# UC3843_Buck.net
KiCad netlist of a schematic drawn in Altium Designer
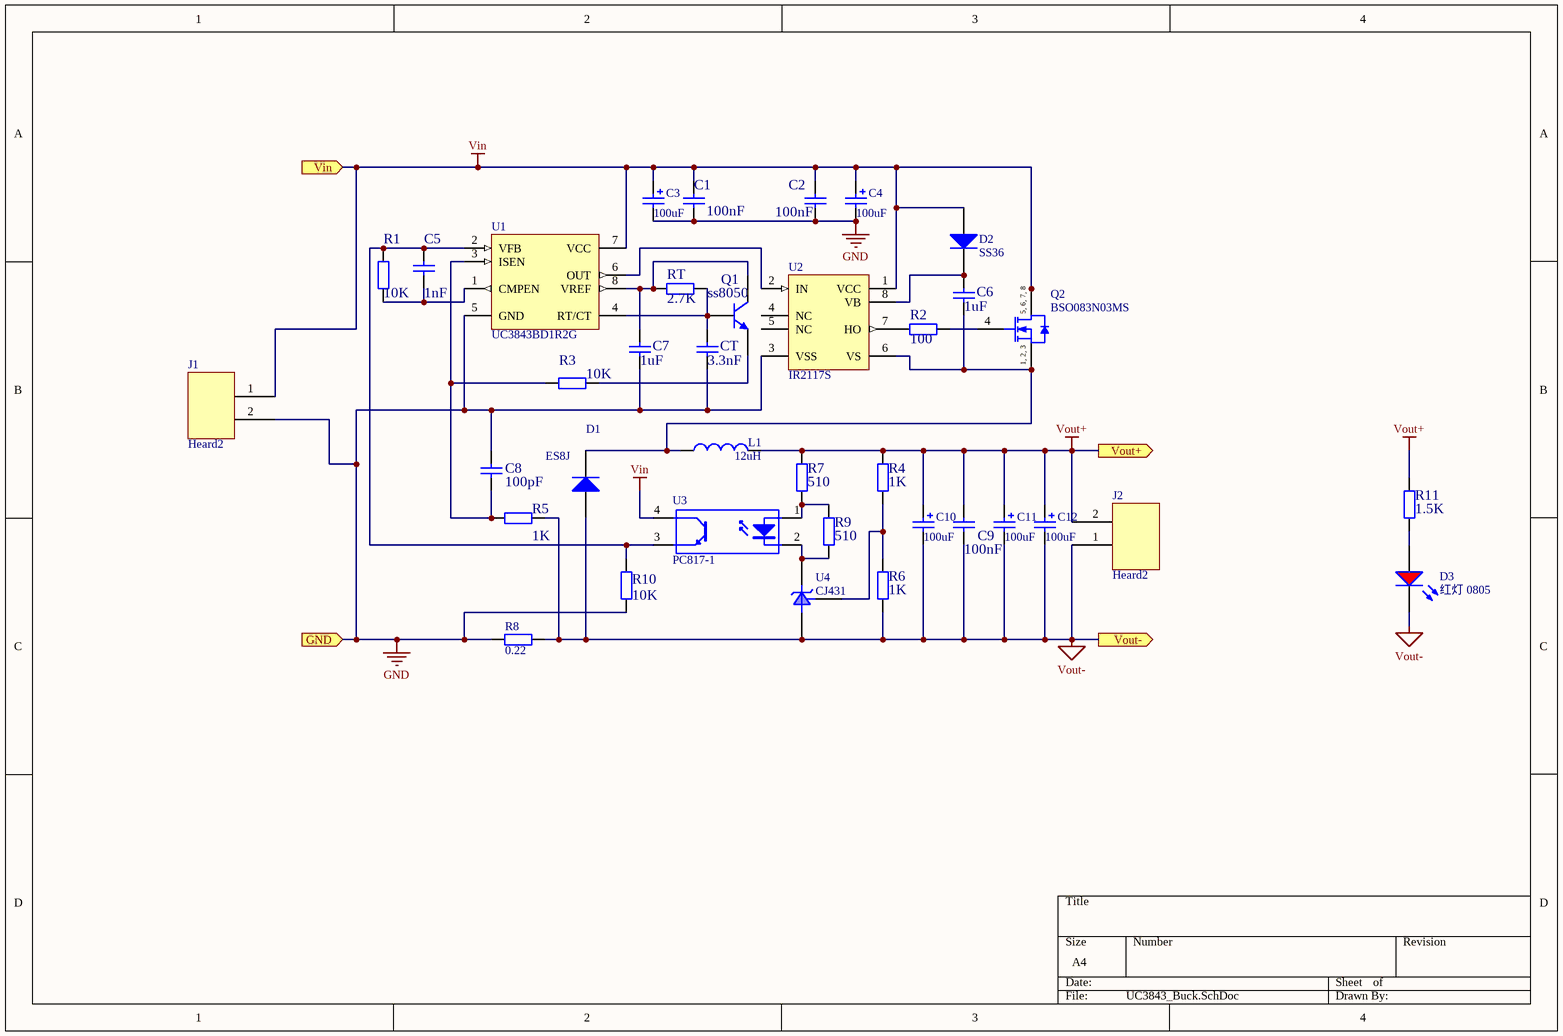
[diagram p0: UC3843_Buck.SchDoc]

(export (version "E")
  (design (tool "Eeschema 10.0.6"))
  (components
    (comp (ref "C1")
      (value "100nF")
      (footprint "0805_C")
      (description "贴片电容")
      (libsource (lib "Miscellaneous Devices LC") (part "0805 100nF(104) 10% 50V"))
    )
    (comp (ref "C2")
      (value "100nF")
      (footprint "0805_C")
      (description "贴片电容")
      (libsource (lib "Miscellaneous Devices LC") (part "0805 100nF(104) 10% 50V"))
    )
    (comp (ref "C3")
      (value "100uF")
      (footprint "CASE-B_3528")
      (description "钽电容")
      (libsource (lib "Miscellaneous Devices LC") (part "3528 100uF (107) 10% 6.3V"))
    )
    (comp (ref "C4")
      (value "100uF")
      (footprint "CASE-B_3528")
      (description "钽电容")
      (libsource (lib "Miscellaneous Devices LC") (part "3528 100uF (107) 10% 6.3V"))
    )
    (comp (ref "C5")
      (value "1nF")
      (footprint "0805_C")
      (description "贴片电容")
      (libsource (lib "Miscellaneous Devices LC") (part "0805 100nF(104) 10% 50V"))
    )
    (comp (ref "C6")
      (value "1uF")
      (footprint "0805R")
      (description "Capacitor")
      (fields (field (name "PUBLISHER") "Altium Limited"))
      (libsource (lib "Miscellaneous Devices") (part "Cap"))
    )
    (comp (ref "C7")
      (value "1uF")
      (footprint "0805R")
      (description "Capacitor")
      (fields (field (name "PUBLISHER") "Altium Limited"))
      (libsource (lib "Miscellaneous Devices") (part "Cap"))
    )
    (comp (ref "C8")
      (value "100pF")
      (footprint "0805R")
      (description "Capacitor")
      (fields (field (name "PUBLISHER") "Altium Limited"))
      (libsource (lib "Miscellaneous Devices") (part "Cap"))
    )
    (comp (ref "C9")
      (value "100nF")
      (footprint "0805_C")
      (description "贴片电容")
      (libsource (lib "Miscellaneous Devices LC") (part "0805 100nF(104) 10% 50V"))
    )
    (comp (ref "C10")
      (value "100uF")
      (footprint "CASE-B_3528")
      (description "钽电容")
      (libsource (lib "Miscellaneous Devices LC") (part "3528 100uF (107) 10% 6.3V"))
    )
    (comp (ref "C11")
      (value "100uF")
      (footprint "CASE-B_3528")
      (description "钽电容")
      (libsource (lib "Miscellaneous Devices LC") (part "3528 100uF (107) 10% 6.3V"))
    )
    (comp (ref "C12")
      (value "100uF")
      (footprint "CASE-B_3528")
      (description "钽电容")
      (libsource (lib "Miscellaneous Devices LC") (part "3528 100uF (107) 10% 6.3V"))
    )
    (comp (ref "CT")
      (value "3.3nF")
      (footprint "0805R")
      (description "Capacitor")
      (fields (field (name "PUBLISHER") "Altium Limited"))
      (libsource (lib "Miscellaneous Devices") (part "Cap"))
    )
    (comp (ref "D1")
      (value "ES8J")
      (footprint "SMC(DO-214AB)_S1")
      (description "二极管")
      (libsource (lib "Miscellaneous Devices LC") (part "SMC(DO-214AB) SS36-E3/57T"))
    )
    (comp (ref "D2")
      (value "SS36")
      (footprint "SMC(DO-214AB)_S1")
      (description "二极管")
      (libsource (lib "Miscellaneous Devices LC") (part "SMC(DO-214AB) SS36-E3/57T"))
    )
    (comp (ref "D3")
      (value "红灯 0805")
      (footprint "0805_LED_S1")
      (description "发光二极管")
      (libsource (lib "Miscellaneous Devices LC") (part "0805 红灯"))
    )
    (comp (ref "J1")
      (value "Heard2")
      (footprint "8.5端子")
      (libsource (lib "myIntegrated_Library1") (part "Header2"))
    )
    (comp (ref "J2") (value "Heard2") (footprint "8.5端子") (libsource (lib "") (part "Header2_1")))
    (comp (ref "L1")
      (value "12uH")
      (footprint "L_12uh")
      (libsource (lib "myIntegrated_Library1") (part "L_12uh"))
    )
    (comp (ref "Q1")
      (value "ss8050")
      (footprint "SOT-23(SOT-23-3)")
      (description "三极管")
      (libsource (lib "Miscellaneous Devices LC") (part "SOT-23 SS8050 Y1"))
    )
    (comp (ref "Q2")
      (value "BSO083N03MS")
      (footprint "INF-PG-DSO-8-16_N")
      (fields (field (name "MANUFACTURER") "Infineon") (field (name "PARTNUMBER") "BSO083N03MS G"))
      (libsource (lib "Infineon_Power_MOSFET") (part "BSO083N03MS G"))
    )
    (comp (ref "R1")
      (value "10K")
      (footprint "0805R")
      (description "Resistor")
      (fields (field (name "PUBLISHER") "Altium Limited"))
      (libsource (lib "") (part "Res2_1"))
    )
    (comp (ref "R2")
      (value "100")
      (footprint "0805R")
      (description "Resistor")
      (fields (field (name "PUBLISHER") "Altium Limited"))
      (libsource (lib "") (part "Res2_2"))
    )
    (comp (ref "R3")
      (value "10K")
      (footprint "0805R")
      (description "Resistor")
      (fields (field (name "PUBLISHER") "Altium Limited"))
      (libsource (lib "") (part "Res2_3"))
    )
    (comp (ref "R4")
      (value "1K")
      (footprint "0805R")
      (description "Resistor")
      (fields (field (name "PUBLISHER") "Altium Limited"))
      (libsource (lib "Miscellaneous Devices") (part "Res2"))
    )
    (comp (ref "R5")
      (value "1K")
      (footprint "0805R")
      (description "Resistor")
      (fields (field (name "PUBLISHER") "Altium Limited"))
      (libsource (lib "") (part "Res2_3"))
    )
    (comp (ref "R6")
      (value "1K")
      (footprint "0805R")
      (description "Resistor")
      (fields (field (name "PUBLISHER") "Altium Limited"))
      (libsource (lib "Miscellaneous Devices") (part "Res2"))
    )
    (comp (ref "R7")
      (value "510")
      (footprint "0805R")
      (description "Resistor")
      (fields (field (name "PUBLISHER") "Altium Limited"))
      (libsource (lib "Miscellaneous Devices") (part "Res2"))
    )
    (comp (ref "R8")
      (value "0.22")
      (footprint "水泥电阻")
      (libsource (lib "myIntegrated_Library1") (part "水泥电阻"))
    )
    (comp (ref "R9")
      (value "510")
      (footprint "0805R")
      (description "Resistor")
      (fields (field (name "PUBLISHER") "Altium Limited"))
      (libsource (lib "Miscellaneous Devices") (part "Res2"))
    )
    (comp (ref "R10")
      (value "10K")
      (footprint "0805R")
      (description "Resistor")
      (fields (field (name "PUBLISHER") "Altium Limited"))
      (libsource (lib "") (part "Res2_1"))
    )
    (comp (ref "R11")
      (value "1.5K")
      (footprint "0805R")
      (description "Resistor")
      (fields (field (name "PUBLISHER") "Altium Limited"))
      (libsource (lib "Miscellaneous Devices") (part "Res2"))
    )
    (comp (ref "RT")
      (value "2.7K")
      (footprint "0805R")
      (description "Resistor")
      (fields (field (name "PUBLISHER") "Altium Limited"))
      (libsource (lib "") (part "Res2_2"))
    )
    (comp (ref "U1")
      (value "UC3843BD1R2G")
      (footprint "SOIC-8_150mil")
      (description "开关电源")
      (libsource (lib "Miscellaneous Devices LC") (part "UC3843BD1R2G_[C16414]"))
    )
    (comp (ref "U2")
      (value "IR2117S")
      (footprint "SO-8_N")
      (description "Single Channel Driver")
      (fields (field (name "PUBLISHER") "Altium Limited"))
      (libsource (lib "IR Interface MOSFET Driver") (part "IR2117S"))
    )
    (comp (ref "U3")
      (value "PC817-1")
      (footprint "LC-SMD-4")
      (libsource (lib "myIntegrated_Library1") (part "TLP521"))
    )
    (comp (ref "U4")
      (value "CJ431")
      (footprint "SOT-23(SOT-23-3)")
      (description "电压基准")
      (libsource (lib "Miscellaneous Devices LC") (part "CJ431 0.5%431_[C3113]"))
    )
  )
  (nets
    (net (code "1") (name "GND") (class "Default")
      (node (ref "C1") (pin "1") (pinfunction "1_1") (pintype "passive"))
      (node (ref "C2") (pin "1") (pinfunction "1_1") (pintype "passive"))
      (node (ref "C3") (pin "2") (pinfunction "2_2") (pintype "passive"))
      (node (ref "C4") (pin "2") (pinfunction "2_2") (pintype "passive"))
      (node (ref "C7") (pin "2") (pinfunction "2_2") (pintype "passive"))
      (node (ref "C8") (pin "2") (pinfunction "2_2") (pintype "passive"))
      (node (ref "CT") (pin "2") (pinfunction "2_2") (pintype "passive"))
      (node (ref "J1") (pin "2") (pinfunction "2_2") (pintype "passive"))
      (node (ref "R10") (pin "2") (pinfunction "2_2") (pintype "passive"))
      (node (ref "R8") (pin "1") (pinfunction "1_1") (pintype "passive"))
      (node (ref "U1") (pin "5") (pinfunction "GND_5") (pintype "power_in"))
      (node (ref "U2") (pin "3") (pinfunction "VSS_3") (pintype "power_in"))
    )
    (net (code "2") (name "Net-(D1-K)") (class "Default")
      (node (ref "C6") (pin "2") (pinfunction "2_2") (pintype "passive"))
      (node (ref "D1") (pin "2") (pinfunction "K_2") (pintype "passive"))
      (node (ref "L1") (pin "1") (pinfunction "1_1") (pintype "passive"))
      (node (ref "Q2") (pin "1") (pinfunction "SOURCE_1") (pintype "passive"))
      (node (ref "Q2") (pin "2") (pinfunction "SOURCE_2") (pintype "passive"))
      (node (ref "Q2") (pin "3") (pinfunction "SOURCE_3") (pintype "passive"))
      (node (ref "U2") (pin "6") (pinfunction "VS_6") (pintype "power_in"))
    )
    (net (code "3") (name "Net-(D2-K)") (class "Default")
      (node (ref "C6") (pin "1") (pinfunction "1_1") (pintype "passive"))
      (node (ref "D2") (pin "2") (pinfunction "K_2") (pintype "passive"))
      (node (ref "U2") (pin "8") (pinfunction "VB_8") (pintype "power_in"))
    )
    (net (code "4") (name "Net-(D3-PadA)") (class "Default")
      (node (ref "D3") (pin "A") (pinfunction "A_A") (pintype "passive"))
      (node (ref "R11") (pin "1") (pinfunction "1_1") (pintype "passive"))
    )
    (net (code "5") (name "Net-(Q1-B)") (class "Default")
      (node (ref "CT") (pin "1") (pinfunction "1_1") (pintype "passive"))
      (node (ref "Q1") (pin "1") (pinfunction "B_1") (pintype "passive"))
      (node (ref "RT") (pin "2") (pinfunction "2_2") (pintype "passive"))
      (node (ref "U1") (pin "4") (pinfunction "RT/CT_4") (pintype "passive"))
    )
    (net (code "6") (name "Net-(Q1-C)") (class "Default")
      (node (ref "C7") (pin "1") (pinfunction "1_1") (pintype "passive"))
      (node (ref "Q1") (pin "3") (pinfunction "C_3") (pintype "passive"))
      (node (ref "RT") (pin "1") (pinfunction "1_1") (pintype "passive"))
      (node (ref "U1") (pin "8") (pinfunction "VREF_8") (pintype "output"))
    )
    (net (code "7") (name "Net-(Q1-E)") (class "Default")
      (node (ref "Q1") (pin "2") (pinfunction "E_2") (pintype "passive"))
      (node (ref "R3") (pin "1") (pinfunction "1_1") (pintype "passive"))
    )
    (net (code "8") (name "Net-(Q2-GATE)") (class "Default")
      (node (ref "Q2") (pin "4") (pinfunction "GATE_4") (pintype "passive"))
      (node (ref "R2") (pin "2") (pinfunction "2_2") (pintype "passive"))
    )
    (net (code "9") (name "Net-(U1-CMPEN)") (class "Default")
      (node (ref "C5") (pin "1") (pinfunction "1_1") (pintype "passive"))
      (node (ref "R1") (pin "2") (pinfunction "2_2") (pintype "passive"))
      (node (ref "U1") (pin "1") (pinfunction "CMPEN_1") (pintype "output"))
    )
    (net (code "10") (name "Net-(U1-ISEN)") (class "Default")
      (node (ref "C8") (pin "1") (pinfunction "1_1") (pintype "passive"))
      (node (ref "R3") (pin "2") (pinfunction "2_2") (pintype "passive"))
      (node (ref "R5") (pin "2") (pinfunction "2_2") (pintype "passive"))
      (node (ref "U1") (pin "3") (pinfunction "ISEN_3") (pintype "input"))
    )
    (net (code "11") (name "Net-(U1-OUT)") (class "Default")
      (node (ref "U1") (pin "6") (pinfunction "OUT_6") (pintype "output"))
      (node (ref "U2") (pin "2") (pinfunction "IN_2") (pintype "input"))
    )
    (net (code "12") (name "Net-(U1-VFB)") (class "Default")
      (node (ref "C5") (pin "2") (pinfunction "2_2") (pintype "passive"))
      (node (ref "R1") (pin "1") (pinfunction "1_1") (pintype "passive"))
      (node (ref "R10") (pin "1") (pinfunction "1_1") (pintype "passive"))
      (node (ref "U1") (pin "2") (pinfunction "VFB_2") (pintype "input"))
      (node (ref "U3") (pin "3") (pinfunction "E_3") (pintype "passive"))
    )
    (net (code "13") (name "Net-(U2-HO)") (class "Default")
      (node (ref "R2") (pin "1") (pinfunction "1_1") (pintype "passive"))
      (node (ref "U2") (pin "7") (pinfunction "HO_7") (pintype "output"))
    )
    (net (code "14") (name "Net-(U3-A)") (class "Default")
      (node (ref "R7") (pin "1") (pinfunction "1_1") (pintype "passive"))
      (node (ref "R9") (pin "2") (pinfunction "2_2") (pintype "passive"))
      (node (ref "U3") (pin "1") (pinfunction "A_1") (pintype "passive"))
    )
    (net (code "15") (name "Net-(U3-K)") (class "Default")
      (node (ref "R9") (pin "1") (pinfunction "1_1") (pintype "passive"))
      (node (ref "U3") (pin "2") (pinfunction "K_2") (pintype "passive"))
      (node (ref "U4") (pin "2") (pinfunction "K_2") (pintype "passive"))
    )
    (net (code "16") (name "Net-(U4-R)") (class "Default")
      (node (ref "R4") (pin "1") (pinfunction "1_1") (pintype "passive"))
      (node (ref "R6") (pin "2") (pinfunction "2_2") (pintype "passive"))
      (node (ref "U4") (pin "1") (pinfunction "R_1") (pintype "passive"))
    )
    (net (code "17") (name "Vin") (class "Default")
      (node (ref "C1") (pin "2") (pinfunction "2_2") (pintype "passive"))
      (node (ref "C2") (pin "2") (pinfunction "2_2") (pintype "passive"))
      (node (ref "C3") (pin "1") (pinfunction "1_1") (pintype "passive"))
      (node (ref "C4") (pin "1") (pinfunction "1_1") (pintype "passive"))
      (node (ref "D2") (pin "1") (pinfunction "A_1") (pintype "passive"))
      (node (ref "J1") (pin "1") (pinfunction "1_1") (pintype "passive"))
      (node (ref "Q2") (pin "5") (pinfunction "DRAIN_5") (pintype "passive"))
      (node (ref "Q2") (pin "6") (pinfunction "DRAIN_6") (pintype "passive"))
      (node (ref "Q2") (pin "7") (pinfunction "DRAIN_7") (pintype "passive"))
      (node (ref "Q2") (pin "8") (pinfunction "DRAIN_8") (pintype "passive"))
      (node (ref "U1") (pin "7") (pinfunction "VCC_7") (pintype "power_in"))
      (node (ref "U2") (pin "1") (pinfunction "VCC_1") (pintype "power_in"))
      (node (ref "U3") (pin "4") (pinfunction "C_4") (pintype "passive"))
    )
    (net (code "18") (name "Vout+") (class "Default")
      (node (ref "C10") (pin "1") (pinfunction "1_1") (pintype "passive"))
      (node (ref "C11") (pin "1") (pinfunction "1_1") (pintype "passive"))
      (node (ref "C12") (pin "1") (pinfunction "1_1") (pintype "passive"))
      (node (ref "C9") (pin "2") (pinfunction "2_2") (pintype "passive"))
      (node (ref "J2") (pin "2") (pinfunction "2_2") (pintype "passive"))
      (node (ref "L1") (pin "2") (pinfunction "2_2") (pintype "passive"))
      (node (ref "R11") (pin "2") (pinfunction "2_2") (pintype "passive"))
      (node (ref "R4") (pin "2") (pinfunction "2_2") (pintype "passive"))
      (node (ref "R7") (pin "2") (pinfunction "2_2") (pintype "passive"))
    )
    (net (code "19") (name "Vout-") (class "Default")
      (node (ref "C10") (pin "2") (pinfunction "2_2") (pintype "passive"))
      (node (ref "C11") (pin "2") (pinfunction "2_2") (pintype "passive"))
      (node (ref "C12") (pin "2") (pinfunction "2_2") (pintype "passive"))
      (node (ref "C9") (pin "1") (pinfunction "1_1") (pintype "passive"))
      (node (ref "D1") (pin "1") (pinfunction "A_1") (pintype "passive"))
      (node (ref "D3") (pin "K") (pinfunction "K_K") (pintype "passive"))
      (node (ref "J2") (pin "1") (pinfunction "1_1") (pintype "passive"))
      (node (ref "R5") (pin "1") (pinfunction "1_1") (pintype "passive"))
      (node (ref "R6") (pin "1") (pinfunction "1_1") (pintype "passive"))
      (node (ref "R8") (pin "2") (pinfunction "2_2") (pintype "passive"))
      (node (ref "U4") (pin "3") (pinfunction "A_3") (pintype "passive"))
    )
    (net (code "20") (name "unconnected-(U2-NC-Pad4)") (class "Default")
      (node (ref "U2") (pin "4") (pinfunction "NC_4") (pintype "passive"))
    )
    (net (code "21") (name "unconnected-(U2-NC-Pad5)") (class "Default")
      (node (ref "U2") (pin "5") (pinfunction "NC_5") (pintype "passive"))
    )
  )
)
